# power_bus.net
KiCad netlist of a schematic drawn in EAGLE
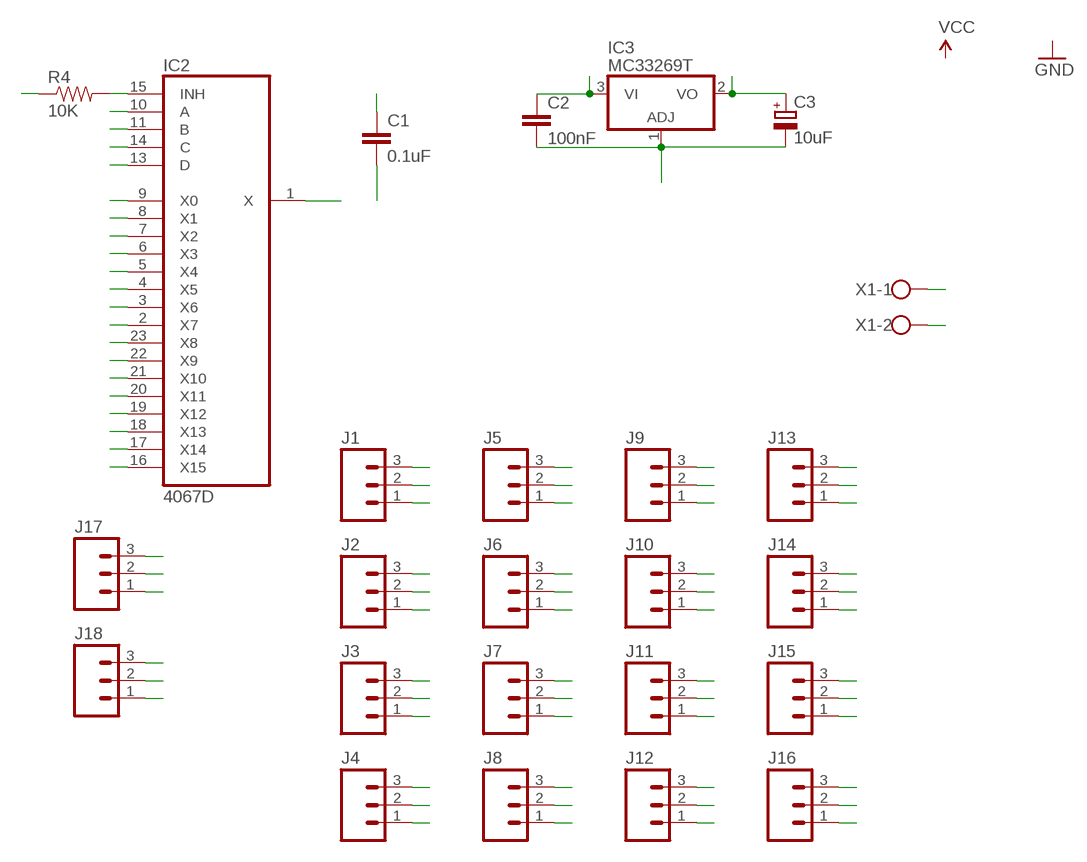
[diagram p0: schematic, sheet 1]

(export (version "E")
  (design (tool "Eeschema 10.0.6"))
  (components
    (comp (ref "C1")
      (value "0.1uF")
      (footprint "eagle-import:CAP-PTH-SMALLEZ")
      (libsource (lib "eagle-import") (part "CAPEZ"))
    )
    (comp (ref "C2")
      (value "100nF")
      (footprint "eagle-import:CAP-PTH-SMALLEZ")
      (libsource (lib "eagle-import") (part "CAPEZ"))
    )
    (comp (ref "C3")
      (value "10uF")
      (footprint "eagle-import:E5-4")
      (libsource (lib "eagle-import") (part "CPOL-EUE5-4"))
    )
    (comp (ref "IC2")
      (value "4067D")
      (footprint "eagle-import:SO24W")
      (libsource (lib "eagle-import") (part "4067D"))
    )
    (comp (ref "IC3")
      (value "MC33269T")
      (footprint "eagle-import:TO220V")
      (libsource (lib "eagle-import") (part "MC33269?T"))
    )
    (comp (ref "J1")
      (value "M03JST-PTH-VERT")
      (footprint "eagle-import:JST-3-PTH-VERT")
      (libsource (lib "eagle-import") (part "M03JST-PTH-VERT"))
    )
    (comp (ref "J2")
      (value "M03JST-PTH-VERT")
      (footprint "eagle-import:JST-3-PTH-VERT")
      (libsource (lib "eagle-import") (part "M03JST-PTH-VERT"))
    )
    (comp (ref "J3")
      (value "M03JST-PTH-VERT")
      (footprint "eagle-import:JST-3-PTH-VERT")
      (libsource (lib "eagle-import") (part "M03JST-PTH-VERT"))
    )
    (comp (ref "J4")
      (value "M03JST-PTH-VERT")
      (footprint "eagle-import:JST-3-PTH-VERT")
      (libsource (lib "eagle-import") (part "M03JST-PTH-VERT"))
    )
    (comp (ref "J5")
      (value "M03JST-PTH-VERT")
      (footprint "eagle-import:JST-3-PTH-VERT")
      (libsource (lib "eagle-import") (part "M03JST-PTH-VERT"))
    )
    (comp (ref "J6")
      (value "M03JST-PTH-VERT")
      (footprint "eagle-import:JST-3-PTH-VERT")
      (libsource (lib "eagle-import") (part "M03JST-PTH-VERT"))
    )
    (comp (ref "J7")
      (value "M03JST-PTH-VERT")
      (footprint "eagle-import:JST-3-PTH-VERT")
      (libsource (lib "eagle-import") (part "M03JST-PTH-VERT"))
    )
    (comp (ref "J8")
      (value "M03JST-PTH-VERT")
      (footprint "eagle-import:JST-3-PTH-VERT")
      (libsource (lib "eagle-import") (part "M03JST-PTH-VERT"))
    )
    (comp (ref "J9")
      (value "M03JST-PTH-VERT")
      (footprint "eagle-import:JST-3-PTH-VERT")
      (libsource (lib "eagle-import") (part "M03JST-PTH-VERT"))
    )
    (comp (ref "J10")
      (value "M03JST-PTH-VERT")
      (footprint "eagle-import:JST-3-PTH-VERT")
      (libsource (lib "eagle-import") (part "M03JST-PTH-VERT"))
    )
    (comp (ref "J11")
      (value "M03JST-PTH-VERT")
      (footprint "eagle-import:JST-3-PTH-VERT")
      (libsource (lib "eagle-import") (part "M03JST-PTH-VERT"))
    )
    (comp (ref "J12")
      (value "M03JST-PTH-VERT")
      (footprint "eagle-import:JST-3-PTH-VERT")
      (libsource (lib "eagle-import") (part "M03JST-PTH-VERT"))
    )
    (comp (ref "J13")
      (value "M03JST-PTH-VERT")
      (footprint "eagle-import:JST-3-PTH-VERT")
      (libsource (lib "eagle-import") (part "M03JST-PTH-VERT"))
    )
    (comp (ref "J14")
      (value "M03JST-PTH-VERT")
      (footprint "eagle-import:JST-3-PTH-VERT")
      (libsource (lib "eagle-import") (part "M03JST-PTH-VERT"))
    )
    (comp (ref "J15")
      (value "M03JST-PTH-VERT")
      (footprint "eagle-import:JST-3-PTH-VERT")
      (libsource (lib "eagle-import") (part "M03JST-PTH-VERT"))
    )
    (comp (ref "J16")
      (value "M03JST-PTH-VERT")
      (footprint "eagle-import:JST-3-PTH-VERT")
      (libsource (lib "eagle-import") (part "M03JST-PTH-VERT"))
    )
    (comp (ref "J17")
      (value "M03PTH")
      (footprint "eagle-import:1X03")
      (libsource (lib "eagle-import") (part "M03PTH"))
    )
    (comp (ref "J18")
      (value "M03PTH")
      (footprint "eagle-import:1X03")
      (libsource (lib "eagle-import") (part "M03PTH"))
    )
    (comp (ref "R4")
      (value "10K")
      (footprint "eagle-import:AXIAL-0.3")
      (libsource (lib "eagle-import") (part "RESISTORAXIAL-0.3"))
    )
    (comp (ref "X1")
      (value "W237-102")
      (footprint "eagle-import:W237-102")
      (fields (field (name "MPN") "237-102"))
      (libsource (lib "eagle-import") (part "W237-102"))
    )
  )
  (nets
    (net (code "1") (name "/MUX0") (class "Default")
      (node (ref "IC2") (pin "9") (pinfunction "X0_9") (pintype "input"))
      (node (ref "J1") (pin "3") (pinfunction "3_3") (pintype "passive"))
    )
    (net (code "2") (name "/MUX1") (class "Default")
      (node (ref "IC2") (pin "8") (pinfunction "X1_8") (pintype "input"))
      (node (ref "J2") (pin "3") (pinfunction "3_3") (pintype "passive"))
    )
    (net (code "3") (name "/MUX2") (class "Default")
      (node (ref "IC2") (pin "7") (pinfunction "X2_7") (pintype "input"))
      (node (ref "J3") (pin "3") (pinfunction "3_3") (pintype "passive"))
    )
    (net (code "4") (name "/MUX3") (class "Default")
      (node (ref "IC2") (pin "6") (pinfunction "X3_6") (pintype "input"))
      (node (ref "J4") (pin "3") (pinfunction "3_3") (pintype "passive"))
    )
    (net (code "5") (name "/MUX4") (class "Default")
      (node (ref "IC2") (pin "5") (pinfunction "X4_5") (pintype "input"))
      (node (ref "J5") (pin "3") (pinfunction "3_3") (pintype "passive"))
    )
    (net (code "6") (name "/MUX5") (class "Default")
      (node (ref "IC2") (pin "4") (pinfunction "X5_4") (pintype "input"))
      (node (ref "J6") (pin "3") (pinfunction "3_3") (pintype "passive"))
    )
    (net (code "7") (name "/MUX6") (class "Default")
      (node (ref "IC2") (pin "3") (pinfunction "X6_3") (pintype "input"))
      (node (ref "J7") (pin "3") (pinfunction "3_3") (pintype "passive"))
    )
    (net (code "8") (name "/MUX7") (class "Default")
      (node (ref "IC2") (pin "2") (pinfunction "X7_2") (pintype "input"))
      (node (ref "J8") (pin "3") (pinfunction "3_3") (pintype "passive"))
    )
    (net (code "9") (name "/MUX8") (class "Default")
      (node (ref "IC2") (pin "23") (pinfunction "X8_23") (pintype "input"))
      (node (ref "J9") (pin "3") (pinfunction "3_3") (pintype "passive"))
    )
    (net (code "10") (name "/MUX9") (class "Default")
      (node (ref "IC2") (pin "22") (pinfunction "X9_22") (pintype "input"))
      (node (ref "J10") (pin "3") (pinfunction "3_3") (pintype "passive"))
    )
    (net (code "11") (name "/MUX10") (class "Default")
      (node (ref "IC2") (pin "21") (pinfunction "X10_21") (pintype "input"))
      (node (ref "J11") (pin "3") (pinfunction "3_3") (pintype "passive"))
    )
    (net (code "12") (name "/MUX11") (class "Default")
      (node (ref "IC2") (pin "20") (pinfunction "X11_20") (pintype "input"))
      (node (ref "J12") (pin "3") (pinfunction "3_3") (pintype "passive"))
    )
    (net (code "13") (name "/MUX12") (class "Default")
      (node (ref "IC2") (pin "19") (pinfunction "X12_19") (pintype "input"))
      (node (ref "J13") (pin "3") (pinfunction "3_3") (pintype "passive"))
    )
    (net (code "14") (name "/MUX13") (class "Default")
      (node (ref "IC2") (pin "18") (pinfunction "X13_18") (pintype "input"))
      (node (ref "J14") (pin "3") (pinfunction "3_3") (pintype "passive"))
    )
    (net (code "15") (name "/MUX14") (class "Default")
      (node (ref "IC2") (pin "17") (pinfunction "X14_17") (pintype "input"))
      (node (ref "J15") (pin "3") (pinfunction "3_3") (pintype "passive"))
    )
    (net (code "16") (name "/MUX15") (class "Default")
      (node (ref "IC2") (pin "16") (pinfunction "X15_16") (pintype "input"))
      (node (ref "J16") (pin "3") (pinfunction "3_3") (pintype "passive"))
    )
    (net (code "17") (name "/MUX_A") (class "Default")
      (node (ref "IC2") (pin "10") (pinfunction "A_10") (pintype "input"))
      (node (ref "J17") (pin "1") (pinfunction "1_1") (pintype "passive"))
    )
    (net (code "18") (name "/MUX_B") (class "Default")
      (node (ref "IC2") (pin "11") (pinfunction "B_11") (pintype "input"))
      (node (ref "J18") (pin "1") (pinfunction "1_1") (pintype "passive"))
    )
    (net (code "19") (name "/MUX_C") (class "Default")
      (node (ref "IC2") (pin "14") (pinfunction "C_14") (pintype "input"))
      (node (ref "J18") (pin "3") (pinfunction "3_3") (pintype "passive"))
    )
    (net (code "20") (name "/MUX_D") (class "Default")
      (node (ref "IC2") (pin "13") (pinfunction "D_13") (pintype "input"))
      (node (ref "J17") (pin "3") (pinfunction "3_3") (pintype "passive"))
    )
    (net (code "21") (name "/MUX_X") (class "Default")
      (node (ref "IC2") (pin "1") (pinfunction "X_1") (pintype "output"))
      (node (ref "J17") (pin "2") (pinfunction "2_2") (pintype "passive"))
    )
    (net (code "22") (name "/VDD") (class "Default")
      (node (ref "C1") (pin "1") (pinfunction "1_1") (pintype "passive"))
      (node (ref "C3") (pin "+") (pinfunction "+_+") (pintype "passive"))
      (node (ref "IC3") (pin "2") (pinfunction "VO_2") (pintype "passive"))
      (node (ref "J1") (pin "1") (pinfunction "1_1") (pintype "passive"))
      (node (ref "J10") (pin "1") (pinfunction "1_1") (pintype "passive"))
      (node (ref "J11") (pin "1") (pinfunction "1_1") (pintype "passive"))
      (node (ref "J12") (pin "1") (pinfunction "1_1") (pintype "passive"))
      (node (ref "J13") (pin "1") (pinfunction "1_1") (pintype "passive"))
      (node (ref "J14") (pin "1") (pinfunction "1_1") (pintype "passive"))
      (node (ref "J15") (pin "1") (pinfunction "1_1") (pintype "passive"))
      (node (ref "J16") (pin "1") (pinfunction "1_1") (pintype "passive"))
      (node (ref "J2") (pin "1") (pinfunction "1_1") (pintype "passive"))
      (node (ref "J3") (pin "1") (pinfunction "1_1") (pintype "passive"))
      (node (ref "J4") (pin "1") (pinfunction "1_1") (pintype "passive"))
      (node (ref "J5") (pin "1") (pinfunction "1_1") (pintype "passive"))
      (node (ref "J6") (pin "1") (pinfunction "1_1") (pintype "passive"))
      (node (ref "J7") (pin "1") (pinfunction "1_1") (pintype "passive"))
      (node (ref "J8") (pin "1") (pinfunction "1_1") (pintype "passive"))
      (node (ref "J9") (pin "1") (pinfunction "1_1") (pintype "passive"))
    )
    (net (code "23") (name "/VOLTAGE") (class "Default")
      (node (ref "C2") (pin "1") (pinfunction "1_1") (pintype "passive"))
      (node (ref "IC3") (pin "3") (pinfunction "VI_3") (pintype "input"))
      (node (ref "X1") (pin "1") (pinfunction "KL_1") (pintype "passive"))
    )
    (net (code "24") (name "/VSS") (class "Default")
      (node (ref "C1") (pin "2") (pinfunction "2_2") (pintype "passive"))
      (node (ref "C2") (pin "2") (pinfunction "2_2") (pintype "passive"))
      (node (ref "C3") (pin "-") (pinfunction "-_-") (pintype "passive"))
      (node (ref "IC3") (pin "1") (pinfunction "ADJ_1") (pintype "input"))
      (node (ref "J1") (pin "2") (pinfunction "2_2") (pintype "passive"))
      (node (ref "J10") (pin "2") (pinfunction "2_2") (pintype "passive"))
      (node (ref "J11") (pin "2") (pinfunction "2_2") (pintype "passive"))
      (node (ref "J12") (pin "2") (pinfunction "2_2") (pintype "passive"))
      (node (ref "J13") (pin "2") (pinfunction "2_2") (pintype "passive"))
      (node (ref "J14") (pin "2") (pinfunction "2_2") (pintype "passive"))
      (node (ref "J15") (pin "2") (pinfunction "2_2") (pintype "passive"))
      (node (ref "J16") (pin "2") (pinfunction "2_2") (pintype "passive"))
      (node (ref "J18") (pin "2") (pinfunction "2_2") (pintype "passive"))
      (node (ref "J2") (pin "2") (pinfunction "2_2") (pintype "passive"))
      (node (ref "J3") (pin "2") (pinfunction "2_2") (pintype "passive"))
      (node (ref "J4") (pin "2") (pinfunction "2_2") (pintype "passive"))
      (node (ref "J5") (pin "2") (pinfunction "2_2") (pintype "passive"))
      (node (ref "J6") (pin "2") (pinfunction "2_2") (pintype "passive"))
      (node (ref "J7") (pin "2") (pinfunction "2_2") (pintype "passive"))
      (node (ref "J8") (pin "2") (pinfunction "2_2") (pintype "passive"))
      (node (ref "J9") (pin "2") (pinfunction "2_2") (pintype "passive"))
      (node (ref "R4") (pin "P$1") (pinfunction "1_P$1") (pintype "passive"))
      (node (ref "X1") (pin "2") (pinfunction "KL_2") (pintype "passive"))
    )
    (net (code "26") (name "Net-(IC2A-INH)") (class "Default")
      (node (ref "IC2") (pin "15") (pinfunction "INH_15") (pintype "input"))
      (node (ref "R4") (pin "P$2") (pinfunction "2_P$2") (pintype "passive"))
    )
  )
)
